# L298_Motor_Driver_Module.net
KiCad netlist of a schematic drawn in EAGLE
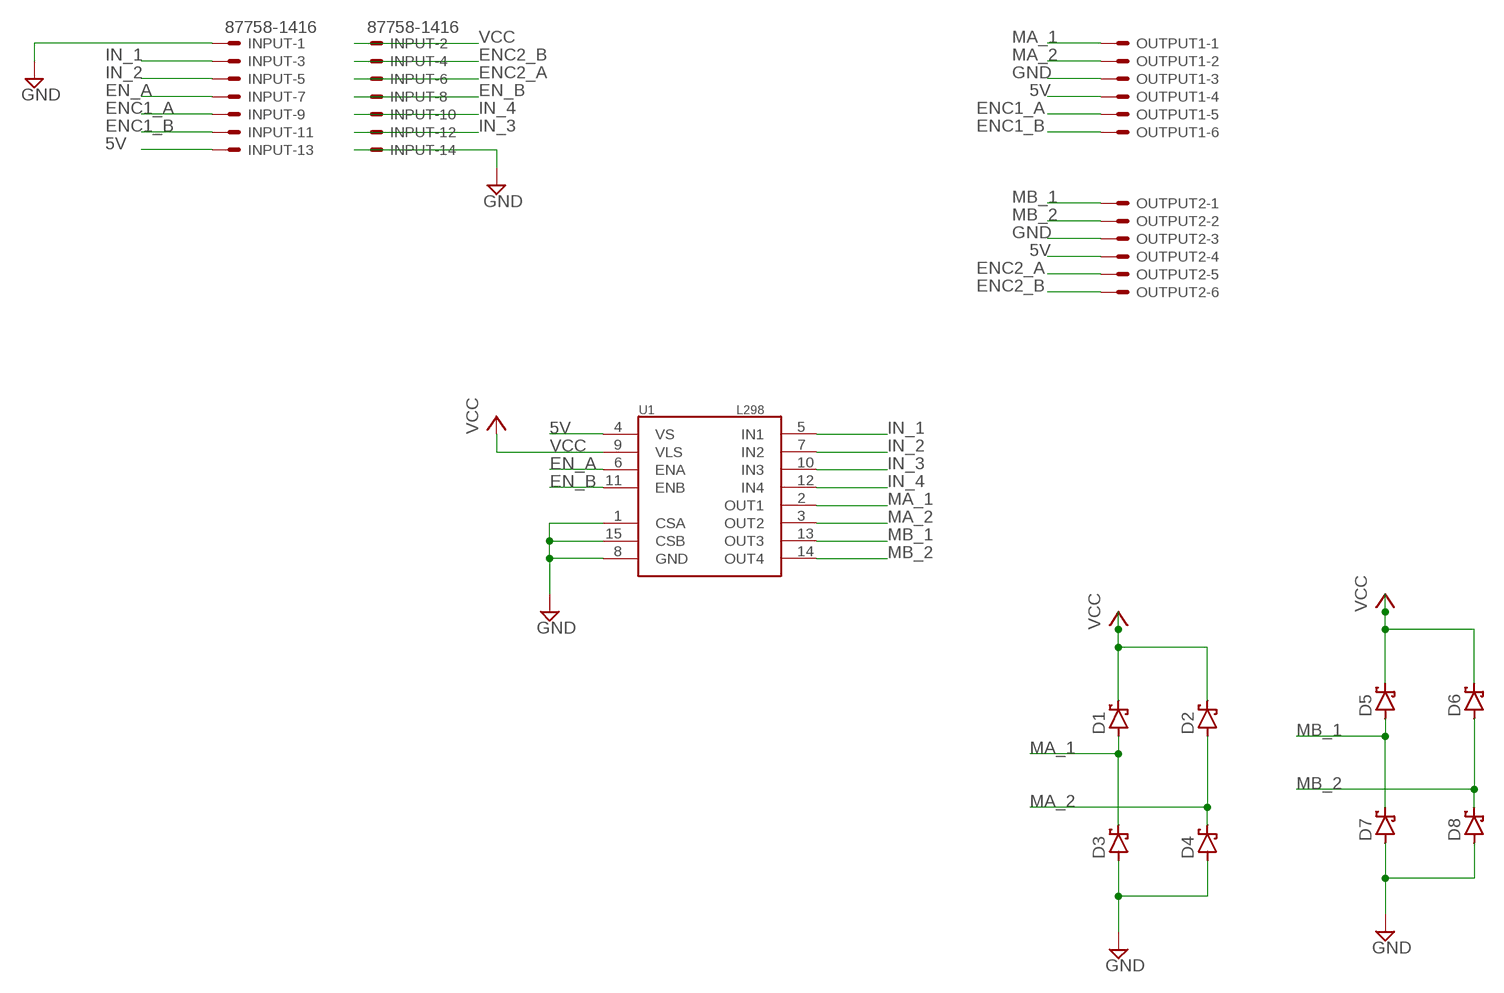
[diagram p0: schematic, sheet 1]

(export (version "E")
  (design (tool "Eeschema 10.0.6"))
  (components
    (comp (ref "D1")
      (value "SCHOTTKY-DIODEDO35-7")
      (footprint "eagle-import:DO35-7")
      (libsource (lib "eagle-import") (part "SCHOTTKY-DIODEDO35-7"))
    )
    (comp (ref "D2")
      (value "SCHOTTKY-DIODEDO35-7")
      (footprint "eagle-import:DO35-7")
      (libsource (lib "eagle-import") (part "SCHOTTKY-DIODEDO35-7"))
    )
    (comp (ref "D3")
      (value "SCHOTTKY-DIODEDO35-7")
      (footprint "eagle-import:DO35-7")
      (libsource (lib "eagle-import") (part "SCHOTTKY-DIODEDO35-7"))
    )
    (comp (ref "D4")
      (value "SCHOTTKY-DIODEDO35-7")
      (footprint "eagle-import:DO35-7")
      (libsource (lib "eagle-import") (part "SCHOTTKY-DIODEDO35-7"))
    )
    (comp (ref "D5")
      (value "SCHOTTKY-DIODEDO35-7")
      (footprint "eagle-import:DO35-7")
      (libsource (lib "eagle-import") (part "SCHOTTKY-DIODEDO35-7"))
    )
    (comp (ref "D6")
      (value "SCHOTTKY-DIODEDO35-7")
      (footprint "eagle-import:DO35-7")
      (libsource (lib "eagle-import") (part "SCHOTTKY-DIODEDO35-7"))
    )
    (comp (ref "D7")
      (value "SCHOTTKY-DIODEDO35-7")
      (footprint "eagle-import:DO35-7")
      (libsource (lib "eagle-import") (part "SCHOTTKY-DIODEDO35-7"))
    )
    (comp (ref "D8")
      (value "SCHOTTKY-DIODEDO35-7")
      (footprint "eagle-import:DO35-7")
      (libsource (lib "eagle-import") (part "SCHOTTKY-DIODEDO35-7"))
    )
    (comp (ref "INPUT")
      (value "87758-1416")
      (footprint "eagle-import:87758-1416")
      (fields (field (name "MF") "MOLEX"))
      (libsource (lib "eagle-import") (part "87758-1416"))
    )
    (comp (ref "OUTPUT1")
      (value "22-23-2061")
      (footprint "eagle-import:22-23-2061")
      (fields (field (name "MF") "MOLEX"))
      (libsource (lib "eagle-import") (part "22-23-2061"))
    )
    (comp (ref "OUTPUT2")
      (value "22-23-2061")
      (footprint "eagle-import:22-23-2061")
      (fields (field (name "MF") "MOLEX"))
      (libsource (lib "eagle-import") (part "22-23-2061"))
    )
    (comp (ref "U1")
      (value "L298")
      (footprint "eagle-import:MULTIWATT15")
      (libsource (lib "eagle-import") (part "L298"))
    )
  )
  (nets
    (net (code "1") (name "/5V") (class "Default")
      (node (ref "INPUT") (pin "13") (pinfunction "S_13") (pintype "passive"))
      (node (ref "OUTPUT1") (pin "4") (pinfunction "S_4") (pintype "passive"))
      (node (ref "OUTPUT2") (pin "4") (pinfunction "S_4") (pintype "passive"))
      (node (ref "U1") (pin "4") (pinfunction "VS_4") (pintype "bidirectional"))
    )
    (net (code "2") (name "/ENC1_A") (class "Default")
      (node (ref "INPUT") (pin "9") (pinfunction "S_9") (pintype "passive"))
      (node (ref "OUTPUT1") (pin "5") (pinfunction "S_5") (pintype "passive"))
    )
    (net (code "3") (name "/ENC1_B") (class "Default")
      (node (ref "INPUT") (pin "11") (pinfunction "S_11") (pintype "passive"))
      (node (ref "OUTPUT1") (pin "6") (pinfunction "S_6") (pintype "passive"))
    )
    (net (code "4") (name "/ENC2_A") (class "Default")
      (node (ref "INPUT") (pin "6") (pinfunction "S_6") (pintype "passive"))
      (node (ref "OUTPUT2") (pin "5") (pinfunction "S_5") (pintype "passive"))
    )
    (net (code "5") (name "/ENC2_B") (class "Default")
      (node (ref "INPUT") (pin "4") (pinfunction "S_4") (pintype "passive"))
      (node (ref "OUTPUT2") (pin "6") (pinfunction "S_6") (pintype "passive"))
    )
    (net (code "6") (name "/EN_A") (class "Default")
      (node (ref "INPUT") (pin "7") (pinfunction "S_7") (pintype "passive"))
      (node (ref "U1") (pin "6") (pinfunction "ENA_6") (pintype "bidirectional"))
    )
    (net (code "7") (name "/EN_B") (class "Default")
      (node (ref "INPUT") (pin "8") (pinfunction "S_8") (pintype "passive"))
      (node (ref "U1") (pin "11") (pinfunction "ENB_11") (pintype "bidirectional"))
    )
    (net (code "8") (name "/IN_1") (class "Default")
      (node (ref "INPUT") (pin "3") (pinfunction "S_3") (pintype "passive"))
      (node (ref "U1") (pin "5") (pinfunction "IN1_5") (pintype "bidirectional"))
    )
    (net (code "9") (name "/IN_2") (class "Default")
      (node (ref "INPUT") (pin "5") (pinfunction "S_5") (pintype "passive"))
      (node (ref "U1") (pin "7") (pinfunction "IN2_7") (pintype "bidirectional"))
    )
    (net (code "10") (name "/IN_3") (class "Default")
      (node (ref "INPUT") (pin "12") (pinfunction "S_12") (pintype "passive"))
      (node (ref "U1") (pin "10") (pinfunction "IN3_10") (pintype "bidirectional"))
    )
    (net (code "11") (name "/IN_4") (class "Default")
      (node (ref "INPUT") (pin "10") (pinfunction "S_10") (pintype "passive"))
      (node (ref "U1") (pin "12") (pinfunction "IN4_12") (pintype "bidirectional"))
    )
    (net (code "12") (name "/MA_1") (class "Default")
      (node (ref "D1") (pin "A") (pinfunction "A_A") (pintype "passive"))
      (node (ref "D3") (pin "C") (pinfunction "C_C") (pintype "passive"))
      (node (ref "OUTPUT1") (pin "1") (pinfunction "S_1") (pintype "passive"))
      (node (ref "U1") (pin "2") (pinfunction "OUT1_2") (pintype "bidirectional"))
    )
    (net (code "13") (name "/MA_2") (class "Default")
      (node (ref "D2") (pin "A") (pinfunction "A_A") (pintype "passive"))
      (node (ref "D4") (pin "C") (pinfunction "C_C") (pintype "passive"))
      (node (ref "OUTPUT1") (pin "2") (pinfunction "S_2") (pintype "passive"))
      (node (ref "U1") (pin "3") (pinfunction "OUT2_3") (pintype "bidirectional"))
    )
    (net (code "14") (name "/MB_1") (class "Default")
      (node (ref "D5") (pin "A") (pinfunction "A_A") (pintype "passive"))
      (node (ref "D7") (pin "C") (pinfunction "C_C") (pintype "passive"))
      (node (ref "OUTPUT2") (pin "1") (pinfunction "S_1") (pintype "passive"))
      (node (ref "U1") (pin "13") (pinfunction "OUT3_13") (pintype "bidirectional"))
    )
    (net (code "15") (name "/MB_2") (class "Default")
      (node (ref "D6") (pin "A") (pinfunction "A_A") (pintype "passive"))
      (node (ref "D8") (pin "C") (pinfunction "C_C") (pintype "passive"))
      (node (ref "OUTPUT2") (pin "2") (pinfunction "S_2") (pintype "passive"))
      (node (ref "U1") (pin "14") (pinfunction "OUT4_14") (pintype "bidirectional"))
    )
    (net (code "16") (name "GND") (class "Default")
      (node (ref "D3") (pin "A") (pinfunction "A_A") (pintype "passive"))
      (node (ref "D4") (pin "A") (pinfunction "A_A") (pintype "passive"))
      (node (ref "D7") (pin "A") (pinfunction "A_A") (pintype "passive"))
      (node (ref "D8") (pin "A") (pinfunction "A_A") (pintype "passive"))
      (node (ref "INPUT") (pin "1") (pinfunction "S_1") (pintype "passive"))
      (node (ref "INPUT") (pin "14") (pinfunction "S_14") (pintype "passive"))
      (node (ref "OUTPUT1") (pin "3") (pinfunction "S_3") (pintype "passive"))
      (node (ref "OUTPUT2") (pin "3") (pinfunction "S_3") (pintype "passive"))
      (node (ref "U1") (pin "1") (pinfunction "CSA_1") (pintype "bidirectional"))
      (node (ref "U1") (pin "15") (pinfunction "CSB_15") (pintype "bidirectional"))
      (node (ref "U1") (pin "8") (pinfunction "GND_8") (pintype "bidirectional"))
    )
    (net (code "17") (name "VCC") (class "Default")
      (node (ref "D1") (pin "C") (pinfunction "C_C") (pintype "passive"))
      (node (ref "D2") (pin "C") (pinfunction "C_C") (pintype "passive"))
      (node (ref "D5") (pin "C") (pinfunction "C_C") (pintype "passive"))
      (node (ref "D6") (pin "C") (pinfunction "C_C") (pintype "passive"))
      (node (ref "INPUT") (pin "2") (pinfunction "S_2") (pintype "passive"))
      (node (ref "U1") (pin "9") (pinfunction "VLS_9") (pintype "bidirectional"))
    )
  )
)
